# MouserSTEAMySummer.net
KiCad netlist of a schematic drawn in EAGLE
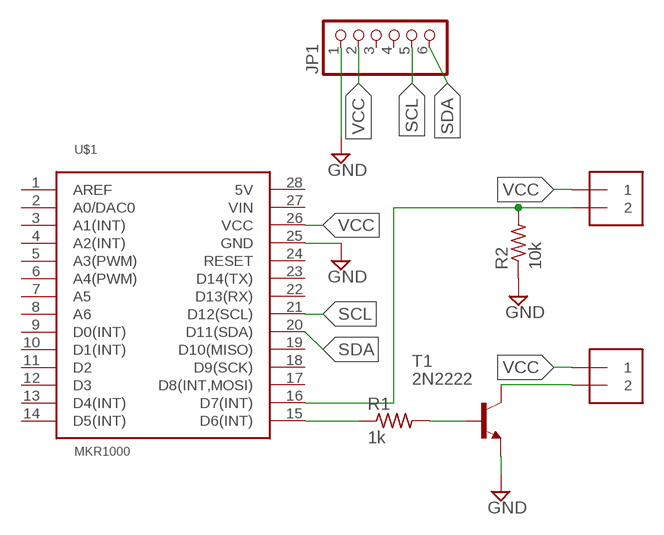
[diagram p0: schematic, sheet 1]

(export (version "E")
  (design (tool "Eeschema 10.0.6"))
  (components
    (comp (ref "BUZZER")
      (value "1X2-3.5MM")
      (footprint "eagle-import:1X2-3.5MM")
      (libsource (lib "eagle-import") (part "1X2-3.5MM"))
    )
    (comp (ref "J1")
      (value "1X2-3.5MM")
      (footprint "eagle-import:1X2-3.5MM")
      (libsource (lib "eagle-import") (part "1X2-3.5MM"))
    )
    (comp (ref "JP1")
      (value "PINHD-1X6B")
      (footprint "eagle-import:1X06-BIG")
      (libsource (lib "eagle-import") (part "PINHD-1X6B"))
    )
    (comp (ref "R1")
      (value "1k")
      (footprint "eagle-import:0207_7")
      (libsource (lib "eagle-import") (part "R-US_0207/7"))
    )
    (comp (ref "R2")
      (value "10k")
      (footprint "eagle-import:0207_7")
      (libsource (lib "eagle-import") (part "R-US_0207/7"))
    )
    (comp (ref "T1")
      (value "2N2222")
      (footprint "eagle-import:TO92-EBC-OVAL")
      (libsource (lib "eagle-import") (part "2N2222"))
    )
    (comp (ref "U$1")
      (value "MKR1000")
      (footprint "eagle-import:MKR1000-SOCKET")
      (libsource (lib "eagle-import") (part "MKR1000"))
    )
  )
  (nets
    (net (code "1") (name "GND") (class "Default")
      (node (ref "JP1") (pin "1") (pinfunction "1_1") (pintype "passive"))
      (node (ref "R2") (pin "1") (pinfunction "1_1") (pintype "passive"))
      (node (ref "T1") (pin "E") (pinfunction "E_E") (pintype "passive"))
      (node (ref "U$1") (pin "25") (pinfunction "GND_25") (pintype "bidirectional"))
    )
    (net (code "2") (name "Net-(BUZZER-Pad2)") (class "Default")
      (node (ref "BUZZER") (pin "2") (pinfunction "2_2") (pintype "passive"))
      (node (ref "T1") (pin "C") (pinfunction "C_C") (pintype "passive"))
    )
    (net (code "3") (name "Net-(R1-Pad2)") (class "Default")
      (node (ref "R1") (pin "2") (pinfunction "2_2") (pintype "passive"))
      (node (ref "T1") (pin "B") (pinfunction "B_B") (pintype "passive"))
    )
    (net (code "4") (name "Net-(U$1-D6(INT))") (class "Default")
      (node (ref "R1") (pin "1") (pinfunction "1_1") (pintype "passive"))
      (node (ref "U$1") (pin "15") (pinfunction "D6(INT)_15") (pintype "bidirectional"))
    )
    (net (code "5") (name "Net-(U$1-D7(INT))") (class "Default")
      (node (ref "J1") (pin "2") (pinfunction "2_2") (pintype "passive"))
      (node (ref "R2") (pin "2") (pinfunction "2_2") (pintype "passive"))
      (node (ref "U$1") (pin "16") (pinfunction "D7(INT)_16") (pintype "bidirectional"))
    )
    (net (code "6") (name "SCL") (class "Default")
      (node (ref "JP1") (pin "5") (pinfunction "5_5") (pintype "passive"))
      (node (ref "U$1") (pin "21") (pinfunction "D12(SCL)_21") (pintype "bidirectional"))
    )
    (net (code "7") (name "SDA") (class "Default")
      (node (ref "JP1") (pin "6") (pinfunction "6_6") (pintype "passive"))
      (node (ref "U$1") (pin "20") (pinfunction "D11(SDA)_20") (pintype "bidirectional"))
    )
    (net (code "8") (name "VCC") (class "Default")
      (node (ref "BUZZER") (pin "1") (pinfunction "1_1") (pintype "passive"))
      (node (ref "J1") (pin "1") (pinfunction "1_1") (pintype "passive"))
      (node (ref "JP1") (pin "2") (pinfunction "2_2") (pintype "passive"))
      (node (ref "U$1") (pin "26") (pinfunction "VCC_26") (pintype "bidirectional"))
    )
    (net (code "9") (name "unconnected-(JP1-Pad3)") (class "Default")
      (node (ref "JP1") (pin "3") (pinfunction "3_3") (pintype "passive"))
    )
    (net (code "10") (name "unconnected-(JP1-Pad4)") (class "Default")
      (node (ref "JP1") (pin "4") (pinfunction "4_4") (pintype "passive"))
    )
    (net (code "11") (name "unconnected-(U$1-5V-Pad28)") (class "Default")
      (node (ref "U$1") (pin "28") (pinfunction "5V_28") (pintype "bidirectional"))
    )
    (net (code "12") (name "unconnected-(U$1-A0{slash}DAC0-Pad2)") (class "Default")
      (node (ref "U$1") (pin "2") (pinfunction "A0/DAC0_2") (pintype "bidirectional"))
    )
    (net (code "13") (name "unconnected-(U$1-A1(INT)-Pad3)") (class "Default")
      (node (ref "U$1") (pin "3") (pinfunction "A1(INT)_3") (pintype "bidirectional"))
    )
    (net (code "14") (name "unconnected-(U$1-A2(INT)-Pad4)") (class "Default")
      (node (ref "U$1") (pin "4") (pinfunction "A2(INT)_4") (pintype "bidirectional"))
    )
    (net (code "15") (name "unconnected-(U$1-A3(PWM)-Pad5)") (class "Default")
      (node (ref "U$1") (pin "5") (pinfunction "A3(PWM)_5") (pintype "bidirectional"))
    )
    (net (code "16") (name "unconnected-(U$1-A4(PWM)-Pad6)") (class "Default")
      (node (ref "U$1") (pin "6") (pinfunction "A4(PWM)_6") (pintype "bidirectional"))
    )
    (net (code "17") (name "unconnected-(U$1-A5-Pad7)") (class "Default")
      (node (ref "U$1") (pin "7") (pinfunction "A5_7") (pintype "bidirectional"))
    )
    (net (code "18") (name "unconnected-(U$1-A6-Pad8)") (class "Default")
      (node (ref "U$1") (pin "8") (pinfunction "A6_8") (pintype "bidirectional"))
    )
    (net (code "19") (name "unconnected-(U$1-AREF-Pad1)") (class "Default")
      (node (ref "U$1") (pin "1") (pinfunction "AREF_1") (pintype "bidirectional"))
    )
    (net (code "20") (name "unconnected-(U$1-D0(INT)-Pad9)") (class "Default")
      (node (ref "U$1") (pin "9") (pinfunction "D0(INT)_9") (pintype "bidirectional"))
    )
    (net (code "21") (name "unconnected-(U$1-D1(INT)-Pad10)") (class "Default")
      (node (ref "U$1") (pin "10") (pinfunction "D1(INT)_10") (pintype "bidirectional"))
    )
    (net (code "22") (name "unconnected-(U$1-D2-Pad11)") (class "Default")
      (node (ref "U$1") (pin "11") (pinfunction "D2_11") (pintype "bidirectional"))
    )
    (net (code "23") (name "unconnected-(U$1-D3-Pad12)") (class "Default")
      (node (ref "U$1") (pin "12") (pinfunction "D3_12") (pintype "bidirectional"))
    )
    (net (code "24") (name "unconnected-(U$1-D4(INT)-Pad13)") (class "Default")
      (node (ref "U$1") (pin "13") (pinfunction "D4(INT)_13") (pintype "bidirectional"))
    )
    (net (code "25") (name "unconnected-(U$1-D5(INT)-Pad14)") (class "Default")
      (node (ref "U$1") (pin "14") (pinfunction "D5(INT)_14") (pintype "bidirectional"))
    )
    (net (code "26") (name "unconnected-(U$1-D8(INT,MOSI)-Pad17)") (class "Default")
      (node (ref "U$1") (pin "17") (pinfunction "D8(INT,MOSI)_17") (pintype "bidirectional"))
    )
    (net (code "27") (name "unconnected-(U$1-D9(SCK)-Pad18)") (class "Default")
      (node (ref "U$1") (pin "18") (pinfunction "D9(SCK)_18") (pintype "bidirectional"))
    )
    (net (code "28") (name "unconnected-(U$1-D10(MISO)-Pad19)") (class "Default")
      (node (ref "U$1") (pin "19") (pinfunction "D10(MISO)_19") (pintype "bidirectional"))
    )
    (net (code "29") (name "unconnected-(U$1-D13(RX)-Pad22)") (class "Default")
      (node (ref "U$1") (pin "22") (pinfunction "D13(RX)_22") (pintype "bidirectional"))
    )
    (net (code "30") (name "unconnected-(U$1-D14(TX)-Pad23)") (class "Default")
      (node (ref "U$1") (pin "23") (pinfunction "D14(TX)_23") (pintype "bidirectional"))
    )
    (net (code "31") (name "unconnected-(U$1-RESET-Pad24)") (class "Default")
      (node (ref "U$1") (pin "24") (pinfunction "RESET_24") (pintype "bidirectional"))
    )
    (net (code "32") (name "unconnected-(U$1-VIN-Pad27)") (class "Default")
      (node (ref "U$1") (pin "27") (pinfunction "VIN_27") (pintype "bidirectional"))
    )
  )
)
